# coqui-v0_2.net
KiCad netlist of a schematic drawn in EAGLE
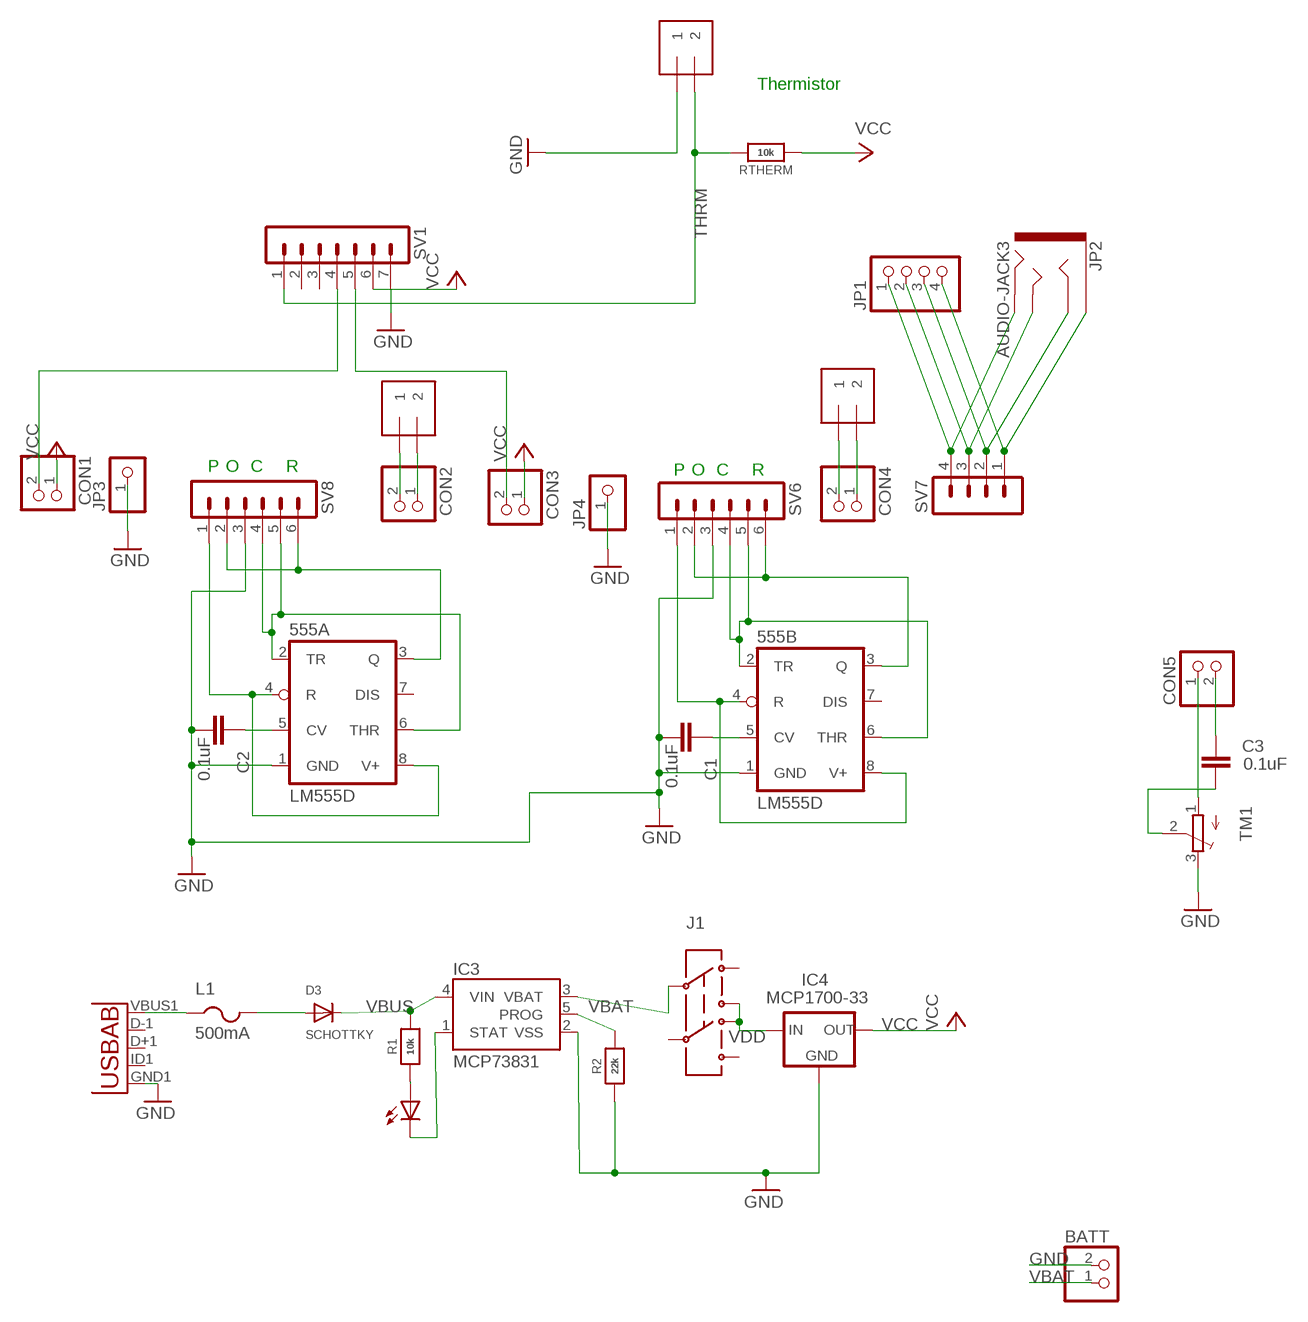
[diagram p0: schematic, sheet 1]

(export (version "E")
  (design (tool "Eeschema 10.0.6"))
  (components
    (comp (ref "555A")
      (value "LM555D")
      (footprint "eagle-import:SO08")
      (libsource (lib "eagle-import") (part "555DLM"))
    )
    (comp (ref "555B")
      (value "LM555D")
      (footprint "eagle-import:SO08")
      (libsource (lib "eagle-import") (part "555DLM"))
    )
    (comp (ref "BATT")
      (value "JST_2PIN-SMT-RA")
      (footprint "eagle-import:JST-PH-2-SMT-RA")
      (libsource (lib "eagle-import") (part "JST_2PIN-SMT-RA"))
    )
    (comp (ref "C1")
      (value "0.1uF")
      (footprint "eagle-import:0603-CAP")
      (libsource (lib "eagle-import") (part "CAP0603-CAP"))
    )
    (comp (ref "C2")
      (value "0.1uF")
      (footprint "eagle-import:0603-CAP")
      (libsource (lib "eagle-import") (part "CAP0603-CAP"))
    )
    (comp (ref "C3")
      (value "0.1uF")
      (footprint "eagle-import:0603-CAP")
      (libsource (lib "eagle-import") (part "CAP0603-CAP"))
    )
    (comp (ref "CHG")
      (value "0805")
      (footprint "eagle-import:CHIPLED_0805")
      (libsource (lib "eagle-import") (part "LEDCHIPLED_0805"))
    )
    (comp (ref "CON1")
      (value "PINHD-1X2")
      (footprint "eagle-import:1X02")
      (libsource (lib "eagle-import") (part "PINHD-1X2"))
    )
    (comp (ref "CON2")
      (value "PINHD-1X2")
      (footprint "eagle-import:1X02")
      (libsource (lib "eagle-import") (part "PINHD-1X2"))
    )
    (comp (ref "CON3")
      (value "PINHD-1X2")
      (footprint "eagle-import:1X02")
      (libsource (lib "eagle-import") (part "PINHD-1X2"))
    )
    (comp (ref "CON4")
      (value "PINHD-1X2")
      (footprint "eagle-import:1X02")
      (libsource (lib "eagle-import") (part "PINHD-1X2"))
    )
    (comp (ref "CON5")
      (value "PINHD-1X2")
      (footprint "eagle-import:1X02")
      (libsource (lib "eagle-import") (part "PINHD-1X2"))
    )
    (comp (ref "D3")
      (value "SCHOTTKY")
      (footprint "eagle-import:SOD-123FL")
      (libsource (lib "eagle-import") (part "DIODE_SOD-123FL"))
    )
    (comp (ref "IC3")
      (value "MCP73831")
      (footprint "eagle-import:SOT23-5")
      (libsource (lib "eagle-import") (part "MCP73831"))
    )
    (comp (ref "IC4")
      (value "MCP1700-33")
      (footprint "eagle-import:SOT89")
      (libsource (lib "eagle-import") (part "MCP1700SOT89"))
    )
    (comp (ref "IN1")
      (value "1X2-3.5MM")
      (footprint "eagle-import:1X2-3.5MM")
      (libsource (lib "eagle-import") (part "1X2-3.5MM"))
    )
    (comp (ref "IN2")
      (value "1X2-3.5MM")
      (footprint "eagle-import:1X2-3.5MM")
      (libsource (lib "eagle-import") (part "1X2-3.5MM"))
    )
    (comp (ref "J1")
      (value "AYZ0202")
      (footprint "eagle-import:AYZ0202")
      (libsource (lib "eagle-import") (part "AYZ0202"))
    )
    (comp (ref "JP1")
      (value "PINHD-1X4/90")
      (footprint "eagle-import:1X04_90")
      (libsource (lib "eagle-import") (part "PINHD-1X4/90"))
    )
    (comp (ref "JP2")
      (value "AUDIO-JACK3")
      (footprint "eagle-import:AUDIO-JACK-TRRS-SMD")
      (libsource (lib "eagle-import") (part "AUDIO-JACK3"))
    )
    (comp (ref "JP3")
      (value "PINHD-1X1")
      (footprint "eagle-import:1X01")
      (libsource (lib "eagle-import") (part "PINHD-1X1"))
    )
    (comp (ref "JP4")
      (value "PINHD-1X1")
      (footprint "eagle-import:1X01")
      (libsource (lib "eagle-import") (part "PINHD-1X1"))
    )
    (comp (ref "L1")
      (value "500mA")
      (footprint "eagle-import:R1206")
      (libsource (lib "eagle-import") (part "PTCFUSE-1206"))
    )
    (comp (ref "R1")
      (value "10k")
      (footprint "eagle-import:0603-NO")
      (libsource (lib "eagle-import") (part "RESISTOR_0603_NOOUT"))
    )
    (comp (ref "R2")
      (value "22k")
      (footprint "eagle-import:0603-NO")
      (libsource (lib "eagle-import") (part "RESISTOR_0603_NOOUT"))
    )
    (comp (ref "RTHERM")
      (value "10k")
      (footprint "eagle-import:0603-NO")
      (libsource (lib "eagle-import") (part "RESISTOR_0603_NOOUT"))
    )
    (comp (ref "SV1")
      (value "MA07-1")
      (footprint "eagle-import:MA07-1")
      (libsource (lib "eagle-import") (part "MA07-1"))
    )
    (comp (ref "SV6")
      (value "MA06-1")
      (footprint "eagle-import:MA06-1")
      (libsource (lib "eagle-import") (part "MA06-1"))
    )
    (comp (ref "SV7")
      (value "MA04-1")
      (footprint "eagle-import:MA04-1")
      (libsource (lib "eagle-import") (part "MA04-1"))
    )
    (comp (ref "SV8")
      (value "MA06-1")
      (footprint "eagle-import:MA06-1")
      (libsource (lib "eagle-import") (part "MA06-1"))
    )
    (comp (ref "THRM")
      (value "1X2-3.5MM")
      (footprint "eagle-import:1X2-3.5MM")
      (libsource (lib "eagle-import") (part "1X2-3.5MM"))
    )
    (comp (ref "TM1")
      (value "TRIMPOTTC33X")
      (footprint "eagle-import:TC33X")
      (libsource (lib "eagle-import") (part "TRIMPOTTC33X"))
    )
    (comp (ref "U$4")
      (value "USB-AB\"\"")
      (footprint "eagle-import:USB-AB-MICRO-SMD_V02_BOSS")
      (libsource (lib "eagle-import") (part "USB-AB{dblquote}{dblquote}"))
    )
  )
  (nets
    (net (code "1") (name "/THRM") (class "Default")
      (node (ref "RTHERM") (pin "2") (pinfunction "2_2") (pintype "passive"))
      (node (ref "SV1") (pin "1") (pinfunction "1_1") (pintype "passive"))
      (node (ref "THRM") (pin "2") (pinfunction "2_2") (pintype "passive"))
    )
    (net (code "2") (name "/VBAT") (class "Default")
      (node (ref "BATT") (pin "1") (pinfunction "2_1") (pintype "passive"))
      (node (ref "IC3") (pin "3") (pinfunction "VBAT_3") (pintype "power_in"))
      (node (ref "J1") (pin "2") (pinfunction "2_2") (pintype "bidirectional"))
    )
    (net (code "3") (name "/VBUS") (class "Default")
      (node (ref "D3") (pin "C") (pinfunction "C_C") (pintype "passive"))
      (node (ref "IC3") (pin "4") (pinfunction "VIN_4") (pintype "power_in"))
      (node (ref "R1") (pin "2") (pinfunction "2_2") (pintype "passive"))
    )
    (net (code "4") (name "/VDD") (class "Default")
      (node (ref "IC4") (pin "2") (pinfunction "IN_2") (pintype "input"))
      (node (ref "J1") (pin "1") (pinfunction "3_1") (pintype "bidirectional"))
      (node (ref "J1") (pin "6") (pinfunction "4_6") (pintype "bidirectional"))
    )
    (net (code "5") (name "GND") (class "Default")
      (node (ref "555A") (pin "1") (pinfunction "GND_1") (pintype "power_in"))
      (node (ref "555B") (pin "1") (pinfunction "GND_1") (pintype "power_in"))
      (node (ref "BATT") (pin "2") (pinfunction "1_2") (pintype "passive"))
      (node (ref "C1") (pin "1") (pinfunction "1_1") (pintype "passive"))
      (node (ref "C2") (pin "1") (pinfunction "1_1") (pintype "passive"))
      (node (ref "IC3") (pin "2") (pinfunction "VSS_2") (pintype "power_in"))
      (node (ref "IC4") (pin "1") (pinfunction "GND_1") (pintype "input"))
      (node (ref "JP3") (pin "1") (pinfunction "1_1") (pintype "passive"))
      (node (ref "JP4") (pin "1") (pinfunction "1_1") (pintype "passive"))
      (node (ref "R2") (pin "1") (pinfunction "1_1") (pintype "passive"))
      (node (ref "SV1") (pin "7") (pinfunction "7_7") (pintype "passive"))
      (node (ref "SV6") (pin "3") (pinfunction "3_3") (pintype "passive"))
      (node (ref "SV8") (pin "3") (pinfunction "3_3") (pintype "passive"))
      (node (ref "THRM") (pin "1") (pinfunction "1_1") (pintype "passive"))
      (node (ref "TM1") (pin "3") (pinfunction "E_3") (pintype "passive"))
      (node (ref "U$4") (pin "GND1") (pinfunction "GND_GND1") (pintype "bidirectional"))
    )
    (net (code "6") (name "Net-(555A-CV)") (class "Default")
      (node (ref "555A") (pin "5") (pinfunction "CV_5") (pintype "input"))
      (node (ref "C2") (pin "2") (pinfunction "2_2") (pintype "passive"))
    )
    (net (code "7") (name "Net-(555A-Q)") (class "Default")
      (node (ref "555A") (pin "3") (pinfunction "Q_3") (pintype "output"))
      (node (ref "SV8") (pin "2") (pinfunction "2_2") (pintype "passive"))
      (node (ref "SV8") (pin "6") (pinfunction "6_6") (pintype "passive"))
    )
    (net (code "8") (name "Net-(555A-R)") (class "Default")
      (node (ref "555A") (pin "4") (pinfunction "R_4") (pintype "input"))
      (node (ref "555A") (pin "8") (pinfunction "V+_8") (pintype "power_in"))
      (node (ref "SV8") (pin "1") (pinfunction "1_1") (pintype "passive"))
    )
    (net (code "9") (name "Net-(555A-THR)") (class "Default")
      (node (ref "555A") (pin "2") (pinfunction "TR_2") (pintype "input"))
      (node (ref "555A") (pin "6") (pinfunction "THR_6") (pintype "input"))
      (node (ref "SV8") (pin "4") (pinfunction "4_4") (pintype "passive"))
      (node (ref "SV8") (pin "5") (pinfunction "5_5") (pintype "passive"))
    )
    (net (code "10") (name "Net-(555B-CV)") (class "Default")
      (node (ref "555B") (pin "5") (pinfunction "CV_5") (pintype "input"))
      (node (ref "C1") (pin "2") (pinfunction "2_2") (pintype "passive"))
    )
    (net (code "11") (name "Net-(555B-Q)") (class "Default")
      (node (ref "555B") (pin "3") (pinfunction "Q_3") (pintype "output"))
      (node (ref "SV6") (pin "2") (pinfunction "2_2") (pintype "passive"))
      (node (ref "SV6") (pin "6") (pinfunction "6_6") (pintype "passive"))
    )
    (net (code "12") (name "Net-(555B-R)") (class "Default")
      (node (ref "555B") (pin "4") (pinfunction "R_4") (pintype "input"))
      (node (ref "555B") (pin "8") (pinfunction "V+_8") (pintype "power_in"))
      (node (ref "SV6") (pin "1") (pinfunction "1_1") (pintype "passive"))
    )
    (net (code "13") (name "Net-(555B-THR)") (class "Default")
      (node (ref "555B") (pin "2") (pinfunction "TR_2") (pintype "input"))
      (node (ref "555B") (pin "6") (pinfunction "THR_6") (pintype "input"))
      (node (ref "SV6") (pin "4") (pinfunction "4_4") (pintype "passive"))
      (node (ref "SV6") (pin "5") (pinfunction "5_5") (pintype "passive"))
    )
    (net (code "14") (name "Net-(C3-Pad2)") (class "Default")
      (node (ref "C3") (pin "2") (pinfunction "2_2") (pintype "passive"))
      (node (ref "CON5") (pin "2") (pinfunction "2_2") (pintype "passive"))
    )
    (net (code "15") (name "Net-(CHG-PadA)") (class "Default")
      (node (ref "CHG") (pin "A") (pinfunction "A_A") (pintype "passive"))
      (node (ref "R1") (pin "1") (pinfunction "1_1") (pintype "passive"))
    )
    (net (code "16") (name "Net-(CON1-Pad2)") (class "Default")
      (node (ref "CON1") (pin "2") (pinfunction "2_2") (pintype "passive"))
      (node (ref "SV1") (pin "4") (pinfunction "4_4") (pintype "passive"))
    )
    (net (code "17") (name "Net-(CON2-Pad1)") (class "Default")
      (node (ref "CON2") (pin "1") (pinfunction "1_1") (pintype "passive"))
      (node (ref "IN1") (pin "2") (pinfunction "2_2") (pintype "passive"))
    )
    (net (code "18") (name "Net-(CON2-Pad2)") (class "Default")
      (node (ref "CON2") (pin "2") (pinfunction "2_2") (pintype "passive"))
      (node (ref "IN1") (pin "1") (pinfunction "1_1") (pintype "passive"))
    )
    (net (code "19") (name "Net-(CON3-Pad2)") (class "Default")
      (node (ref "CON3") (pin "2") (pinfunction "2_2") (pintype "passive"))
      (node (ref "SV1") (pin "5") (pinfunction "5_5") (pintype "passive"))
    )
    (net (code "20") (name "Net-(CON4-Pad1)") (class "Default")
      (node (ref "CON4") (pin "1") (pinfunction "1_1") (pintype "passive"))
      (node (ref "IN2") (pin "2") (pinfunction "2_2") (pintype "passive"))
    )
    (net (code "21") (name "Net-(CON4-Pad2)") (class "Default")
      (node (ref "CON4") (pin "2") (pinfunction "2_2") (pintype "passive"))
      (node (ref "IN2") (pin "1") (pinfunction "1_1") (pintype "passive"))
    )
    (net (code "22") (name "Net-(D3-PadA)") (class "Default")
      (node (ref "D3") (pin "A") (pinfunction "A_A") (pintype "passive"))
      (node (ref "L1") (pin "2") (pinfunction "2_2") (pintype "passive"))
    )
    (net (code "23") (name "Net-(IC3-PROG)") (class "Default")
      (node (ref "IC3") (pin "5") (pinfunction "PROG_5") (pintype "input"))
      (node (ref "R2") (pin "2") (pinfunction "2_2") (pintype "passive"))
    )
    (net (code "24") (name "Net-(IC3-STAT)") (class "Default")
      (node (ref "CHG") (pin "C") (pinfunction "C_C") (pintype "passive"))
      (node (ref "IC3") (pin "1") (pinfunction "STAT_1") (pintype "output"))
    )
    (net (code "25") (name "Net-(JP1-Pad1)") (class "Default")
      (node (ref "JP1") (pin "1") (pinfunction "1_1") (pintype "passive"))
      (node (ref "JP2") (pin "RING2") (pinfunction "RING2_RING2") (pintype "bidirectional"))
      (node (ref "SV7") (pin "4") (pinfunction "4_4") (pintype "passive"))
    )
    (net (code "26") (name "Net-(JP1-Pad2)") (class "Default")
      (node (ref "JP1") (pin "2") (pinfunction "2_2") (pintype "passive"))
      (node (ref "JP2") (pin "TIP") (pinfunction "TIP_TIP") (pintype "bidirectional"))
      (node (ref "SV7") (pin "3") (pinfunction "3_3") (pintype "passive"))
    )
    (net (code "27") (name "Net-(JP1-Pad3)") (class "Default")
      (node (ref "JP1") (pin "3") (pinfunction "3_3") (pintype "passive"))
      (node (ref "JP2") (pin "RING1") (pinfunction "RING1_RING1") (pintype "bidirectional"))
      (node (ref "SV7") (pin "2") (pinfunction "2_2") (pintype "passive"))
    )
    (net (code "28") (name "Net-(JP1-Pad4)") (class "Default")
      (node (ref "JP1") (pin "4") (pinfunction "4_4") (pintype "passive"))
      (node (ref "JP2") (pin "EARTH") (pinfunction "EARTH_EARTH") (pintype "bidirectional"))
      (node (ref "SV7") (pin "1") (pinfunction "1_1") (pintype "passive"))
    )
    (net (code "29") (name "Net-(TM1-A)") (class "Default")
      (node (ref "CON5") (pin "1") (pinfunction "1_1") (pintype "passive"))
      (node (ref "TM1") (pin "1") (pinfunction "A_1") (pintype "passive"))
    )
    (net (code "30") (name "Net-(TM1-S)") (class "Default")
      (node (ref "C3") (pin "1") (pinfunction "1_1") (pintype "passive"))
      (node (ref "TM1") (pin "2") (pinfunction "S_2") (pintype "passive"))
    )
    (net (code "31") (name "Net-(U$4-VBUS)") (class "Default")
      (node (ref "L1") (pin "1") (pinfunction "1_1") (pintype "passive"))
      (node (ref "U$4") (pin "VBUS1") (pinfunction "VBUS_VBUS1") (pintype "bidirectional"))
    )
    (net (code "32") (name "VCC") (class "Default")
      (node (ref "CON1") (pin "1") (pinfunction "1_1") (pintype "passive"))
      (node (ref "CON3") (pin "1") (pinfunction "1_1") (pintype "passive"))
      (node (ref "IC4") (pin "3") (pinfunction "OUT_3") (pintype "passive"))
      (node (ref "RTHERM") (pin "1") (pinfunction "1_1") (pintype "passive"))
      (node (ref "SV1") (pin "6") (pinfunction "6_6") (pintype "passive"))
    )
    (net (code "33") (name "unconnected-(555A-DIS-Pad7)") (class "Default")
      (node (ref "555A") (pin "7") (pinfunction "DIS_7") (pintype "input"))
    )
    (net (code "34") (name "unconnected-(555B-DIS-Pad7)") (class "Default")
      (node (ref "555B") (pin "7") (pinfunction "DIS_7") (pintype "input"))
    )
    (net (code "35") (name "unconnected-(J1-1-Pad3)") (class "Default")
      (node (ref "J1") (pin "3") (pinfunction "1_3") (pintype "bidirectional"))
    )
    (net (code "36") (name "unconnected-(J1-6-Pad4)") (class "Default")
      (node (ref "J1") (pin "4") (pinfunction "6_4") (pintype "bidirectional"))
    )
    (net (code "37") (name "unconnected-(J1-Pad5)") (class "Default")
      (node (ref "J1") (pin "5") (pinfunction "5_5") (pintype "bidirectional"))
    )
    (net (code "38") (name "unconnected-(SV1-Pad2)") (class "Default")
      (node (ref "SV1") (pin "2") (pinfunction "2_2") (pintype "passive"))
    )
    (net (code "39") (name "unconnected-(SV1-Pad3)") (class "Default")
      (node (ref "SV1") (pin "3") (pinfunction "3_3") (pintype "passive"))
    )
    (net (code "40") (name "unconnected-(U$4-D+-PadD+1)") (class "Default")
      (node (ref "U$4") (pin "D+1") (pinfunction "D+_D+1") (pintype "bidirectional"))
    )
    (net (code "41") (name "unconnected-(U$4-D--PadD-1)") (class "Default")
      (node (ref "U$4") (pin "D-1") (pinfunction "D-_D-1") (pintype "bidirectional"))
    )
    (net (code "42") (name "unconnected-(U$4-USBID-PadID1)") (class "Default")
      (node (ref "U$4") (pin "ID1") (pinfunction "USBID_ID1") (pintype "bidirectional"))
    )
  )
)
